# 1_54inch_e-Paper.net
KiCad netlist of a schematic drawn in Altium Designer
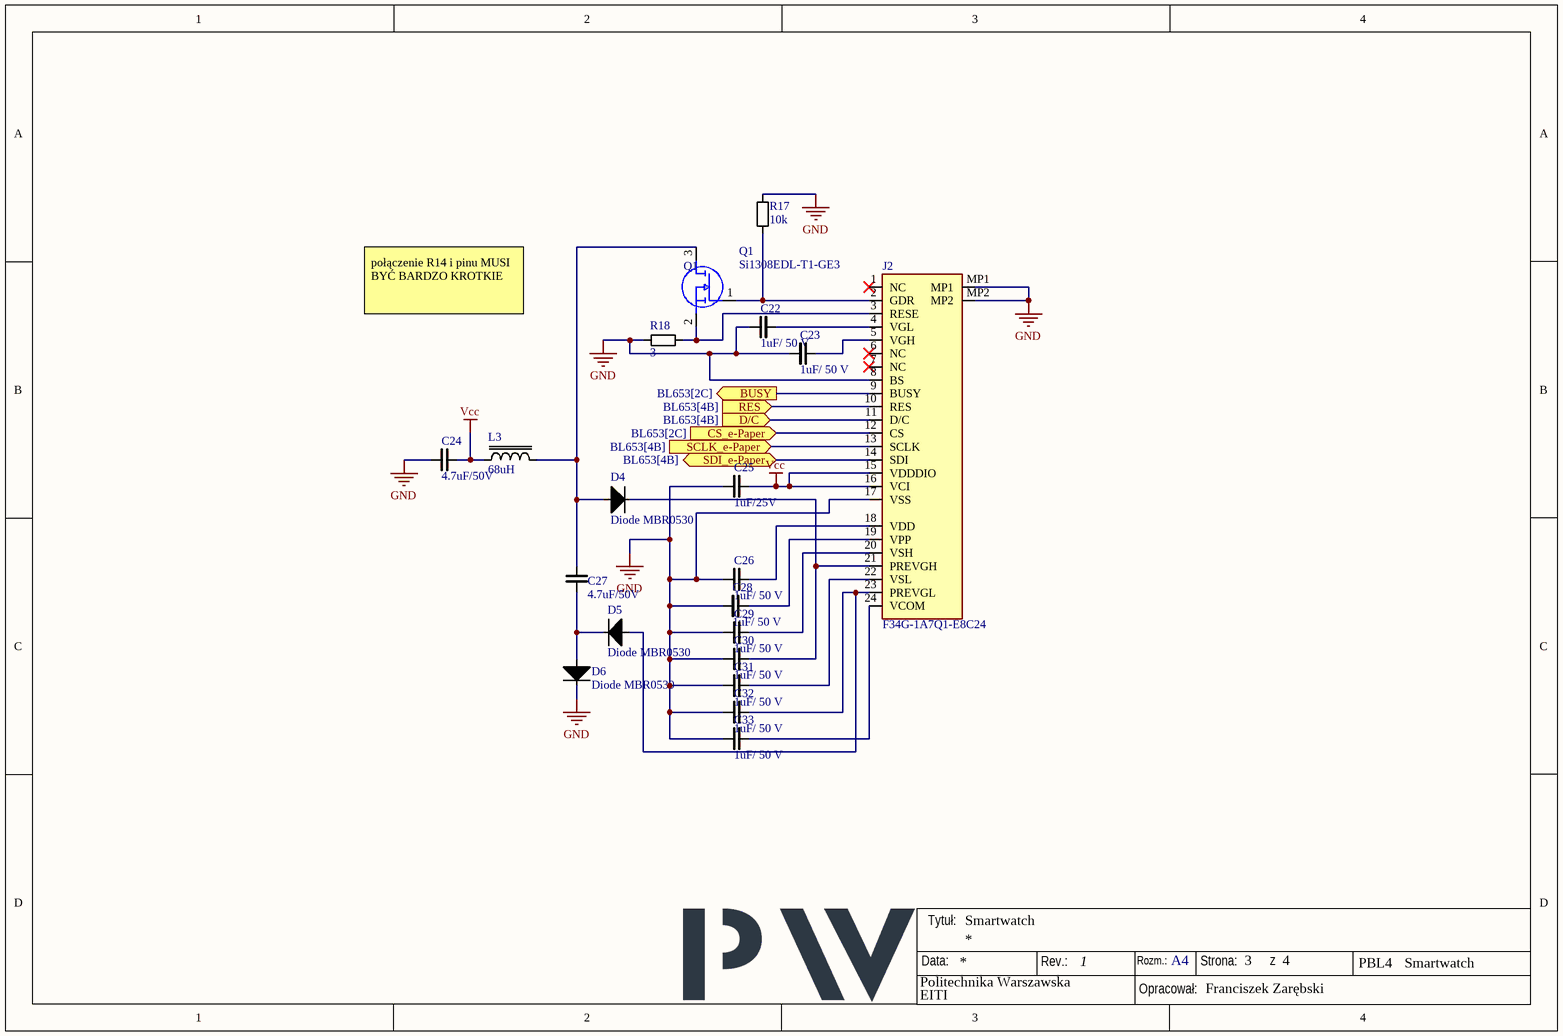
[diagram p0: 1.54inch_e-Paper.SchDoc]

(export (version "E")
  (design (tool "Eeschema 10.0.6"))
  (components
    (comp (ref "C22")
      (value "1uF/ 50 V")
      (footprint "0402_CAP_REFLOW")
      (description "50 V")
      (libsource (lib "e-Paper") (part "Capacitor 1uF/50V"))
    )
    (comp (ref "C23")
      (value "1uF/ 50 V")
      (footprint "0402_CAP_REFLOW")
      (description "50 V")
      (libsource (lib "e-Paper") (part "Capacitor 1uF/50V"))
    )
    (comp (ref "C24")
      (value "4.7uF/50V")
      (footprint "0402_CAP_REFLOW")
      (description "50V")
      (libsource (lib "e-Paper") (part "Capacitor 4.7uF/50V"))
    )
    (comp (ref "C25")
      (value "1uF/25V")
      (footprint "0402_CAP_REFLOW")
      (description "25V")
      (libsource (lib "e-Paper") (part "Capacitor 1uF/25V"))
    )
    (comp (ref "C26")
      (value "1uF/ 50 V")
      (footprint "0402_CAP_REFLOW")
      (description "50 V")
      (libsource (lib "e-Paper") (part "Capacitor 1uF/50V"))
    )
    (comp (ref "C27")
      (value "4.7uF/50V")
      (footprint "0402_CAP_REFLOW")
      (description "50V")
      (libsource (lib "") (part "Capacitor 4.7uF/50V_1"))
    )
    (comp (ref "C28")
      (value "1uF/ 50 V")
      (footprint "0402_CAP_REFLOW")
      (description "50 V")
      (libsource (lib "") (part "Capacitor 1uF/50V_1"))
    )
    (comp (ref "C29")
      (value "1uF/ 50 V")
      (footprint "0402_CAP_REFLOW")
      (description "50 V")
      (libsource (lib "e-Paper") (part "Capacitor 1uF/50V"))
    )
    (comp (ref "C30")
      (value "1uF/ 50 V")
      (footprint "0402_CAP_REFLOW")
      (description "50 V")
      (libsource (lib "e-Paper") (part "Capacitor 1uF/50V"))
    )
    (comp (ref "C31")
      (value "1uF/ 50 V")
      (footprint "0402_CAP_REFLOW")
      (description "50 V")
      (libsource (lib "e-Paper") (part "Capacitor 1uF/50V"))
    )
    (comp (ref "C32")
      (value "1uF/ 50 V")
      (footprint "0402_CAP_REFLOW")
      (description "50 V")
      (libsource (lib "e-Paper") (part "Capacitor 1uF/50V"))
    )
    (comp (ref "C33")
      (value "1uF/ 50 V")
      (footprint "0402_CAP_REFLOW")
      (description "50 V")
      (libsource (lib "e-Paper") (part "Capacitor 1uF/50V"))
    )
    (comp (ref "D4")
      (value "Diode MBR0530")
      (footprint "SOD3716X135N")
      (libsource (lib "e-Paper") (part "Diode MBR0530"))
    )
    (comp (ref "D5")
      (value "Diode MBR0530")
      (footprint "SOD3716X135N")
      (libsource (lib "e-Paper") (part "Diode MBR0530"))
    )
    (comp (ref "D6")
      (value "Diode MBR0530")
      (footprint "SOD3716X135N")
      (libsource (lib "e-Paper") (part "Diode MBR0530"))
    )
    (comp (ref "J2")
      (value "F34G-1A7Q1-E8C24")
      (footprint "F34G1A7Q1E8C24")
      (libsource (lib "e-Paper") (part "FFC & FPC Connectors"))
    )
    (comp (ref "L3")
      (value "68uH")
      (footprint "SRR5828A2R6Y")
      (description "SRR5828A-680M")
      (libsource (lib "e-Paper") (part "InductorA_A"))
    )
    (comp (ref "Q1")
      (value "Si1308EDL-T1-GE3")
      (footprint "SOT65P210X110-3N")
      (fields (field (name "MOUSER PART NUMBER") "78-SI1308EDL-T1-GE3"))
      (libsource (lib "e-Paper") (part "Si1308EDL-T1-GE3"))
    )
    (comp (ref "R17")
      (value "10k")
      (footprint "0402_RES_REFLOW")
      (libsource (lib "BL653u") (part "Resistor R10K"))
    )
    (comp (ref "R18")
      (value "3")
      (footprint "0402_RES_REFLOW")
      (libsource (lib "e-Paper") (part "Resistor R3"))
    )
  )
  (nets
    (net (code "1") (name "/BUSY") (class "Default")
      (node (ref "J2") (pin "9") (pinfunction "BUSY_9") (pintype "passive"))
    )
    (net (code "2") (name "/CS_e-Paper") (class "Default")
      (node (ref "J2") (pin "12") (pinfunction "CS_12") (pintype "passive"))
    )
    (net (code "3") (name "/D{slash}C") (class "Default")
      (node (ref "J2") (pin "11") (pinfunction "D/C_11") (pintype "passive"))
    )
    (net (code "4") (name "/RES") (class "Default")
      (node (ref "J2") (pin "10") (pinfunction "RES_10") (pintype "passive"))
    )
    (net (code "5") (name "/SCLK_e-Paper") (class "Default")
      (node (ref "J2") (pin "13") (pinfunction "SCLK_13") (pintype "passive"))
    )
    (net (code "6") (name "/SDI_e-Paper") (class "Default")
      (node (ref "J2") (pin "14") (pinfunction "SDI_14") (pintype "passive"))
    )
    (net (code "7") (name "GND") (class "Default")
      (node (ref "C22") (pin "1") (pinfunction "1_1") (pintype "passive"))
      (node (ref "C23") (pin "1") (pinfunction "1_1") (pintype "passive"))
      (node (ref "C24") (pin "1") (pinfunction "1_1") (pintype "passive"))
      (node (ref "C25") (pin "1") (pinfunction "1_1") (pintype "passive"))
      (node (ref "C26") (pin "1") (pinfunction "1_1") (pintype "passive"))
      (node (ref "C28") (pin "2") (pinfunction "2_2") (pintype "passive"))
      (node (ref "C29") (pin "1") (pinfunction "1_1") (pintype "passive"))
      (node (ref "C30") (pin "1") (pinfunction "1_1") (pintype "passive"))
      (node (ref "C31") (pin "1") (pinfunction "1_1") (pintype "passive"))
      (node (ref "C32") (pin "1") (pinfunction "1_1") (pintype "passive"))
      (node (ref "C33") (pin "1") (pinfunction "1_1") (pintype "passive"))
      (node (ref "D6") (pin "2") (pinfunction "K_2") (pintype "passive"))
      (node (ref "J2") (pin "17") (pinfunction "VSS_17") (pintype "passive"))
      (node (ref "J2") (pin "8") (pinfunction "BS_8") (pintype "passive"))
      (node (ref "J2") (pin "MP1") (pinfunction "MP1_MP1") (pintype "passive"))
      (node (ref "J2") (pin "MP2") (pinfunction "MP2_MP2") (pintype "passive"))
      (node (ref "R17") (pin "2") (pinfunction "2_2") (pintype "passive"))
      (node (ref "R18") (pin "1") (pinfunction "1_1") (pintype "passive"))
    )
    (net (code "8") (name "Net-(D4-A)") (class "Default")
      (node (ref "C27") (pin "2") (pinfunction "2_2") (pintype "passive"))
      (node (ref "D4") (pin "1") (pinfunction "A_1") (pintype "passive"))
      (node (ref "L3") (pin "1") (pinfunction "1_1") (pintype "passive"))
      (node (ref "Q1") (pin "3") (pinfunction "D_3") (pintype "passive"))
    )
    (net (code "9") (name "Net-(D4-K)") (class "Default")
      (node (ref "C30") (pin "2") (pinfunction "2_2") (pintype "passive"))
      (node (ref "D4") (pin "2") (pinfunction "K_2") (pintype "passive"))
      (node (ref "J2") (pin "21") (pinfunction "PREVGH_21") (pintype "passive"))
    )
    (net (code "10") (name "Net-(D5-A)") (class "Default")
      (node (ref "C32") (pin "2") (pinfunction "2_2") (pintype "passive"))
      (node (ref "D5") (pin "1") (pinfunction "A_1") (pintype "passive"))
      (node (ref "J2") (pin "23") (pinfunction "PREVGL_23") (pintype "passive"))
    )
    (net (code "11") (name "Net-(D5-K)") (class "Default")
      (node (ref "C27") (pin "1") (pinfunction "1_1") (pintype "passive"))
      (node (ref "D5") (pin "2") (pinfunction "K_2") (pintype "passive"))
      (node (ref "D6") (pin "1") (pinfunction "A_1") (pintype "passive"))
    )
    (net (code "12") (name "Net-(J2-GDR)") (class "Default")
      (node (ref "J2") (pin "2") (pinfunction "GDR_2") (pintype "passive"))
      (node (ref "Q1") (pin "1") (pinfunction "G_1") (pintype "passive"))
      (node (ref "R17") (pin "1") (pinfunction "1_1") (pintype "passive"))
    )
    (net (code "13") (name "Net-(J2-RESE)") (class "Default")
      (node (ref "J2") (pin "3") (pinfunction "RESE_3") (pintype "passive"))
      (node (ref "Q1") (pin "2") (pinfunction "S_2") (pintype "passive"))
      (node (ref "R18") (pin "2") (pinfunction "2_2") (pintype "passive"))
    )
    (net (code "14") (name "Net-(J2-VCOM)") (class "Default")
      (node (ref "C33") (pin "2") (pinfunction "2_2") (pintype "passive"))
      (node (ref "J2") (pin "24") (pinfunction "VCOM_24") (pintype "passive"))
    )
    (net (code "15") (name "Net-(J2-VDD)") (class "Default")
      (node (ref "C26") (pin "2") (pinfunction "2_2") (pintype "passive"))
      (node (ref "J2") (pin "18") (pinfunction "VDD_18") (pintype "passive"))
    )
    (net (code "16") (name "Net-(J2-VGH)") (class "Default")
      (node (ref "C23") (pin "2") (pinfunction "2_2") (pintype "passive"))
      (node (ref "J2") (pin "5") (pinfunction "VGH_5") (pintype "passive"))
    )
    (net (code "17") (name "Net-(J2-VGL)") (class "Default")
      (node (ref "C22") (pin "2") (pinfunction "2_2") (pintype "passive"))
      (node (ref "J2") (pin "4") (pinfunction "VGL_4") (pintype "passive"))
    )
    (net (code "18") (name "Net-(J2-VPP)") (class "Default")
      (node (ref "C28") (pin "1") (pinfunction "1_1") (pintype "passive"))
      (node (ref "J2") (pin "19") (pinfunction "VPP_19") (pintype "passive"))
    )
    (net (code "19") (name "Net-(J2-VSH)") (class "Default")
      (node (ref "C29") (pin "2") (pinfunction "2_2") (pintype "passive"))
      (node (ref "J2") (pin "20") (pinfunction "VSH_20") (pintype "passive"))
    )
    (net (code "20") (name "Net-(J2-VSL)") (class "Default")
      (node (ref "C31") (pin "2") (pinfunction "2_2") (pintype "passive"))
      (node (ref "J2") (pin "22") (pinfunction "VSL_22") (pintype "passive"))
    )
    (net (code "21") (name "Vcc") (class "Default")
      (node (ref "C24") (pin "2") (pinfunction "2_2") (pintype "passive"))
      (node (ref "C25") (pin "2") (pinfunction "2_2") (pintype "passive"))
      (node (ref "J2") (pin "15") (pinfunction "VDDDIO_15") (pintype "passive"))
      (node (ref "J2") (pin "16") (pinfunction "VCI_16") (pintype "passive"))
      (node (ref "L3") (pin "2") (pinfunction "2_2") (pintype "passive"))
    )
    (net (code "22") (name "unconnected-(J2-NC-Pad1)") (class "Default")
      (node (ref "J2") (pin "1") (pinfunction "NC_1") (pintype "passive+no_connect"))
    )
    (net (code "23") (name "unconnected-(J2-NC-Pad6)") (class "Default")
      (node (ref "J2") (pin "6") (pinfunction "NC_6") (pintype "passive+no_connect"))
    )
    (net (code "24") (name "unconnected-(J2-NC-Pad7)") (class "Default")
      (node (ref "J2") (pin "7") (pinfunction "NC_7") (pintype "passive+no_connect"))
    )
  )
)
